# Mini_Differential_IR_Endstop_by_DC42.net
KiCad netlist of a schematic drawn in EAGLE
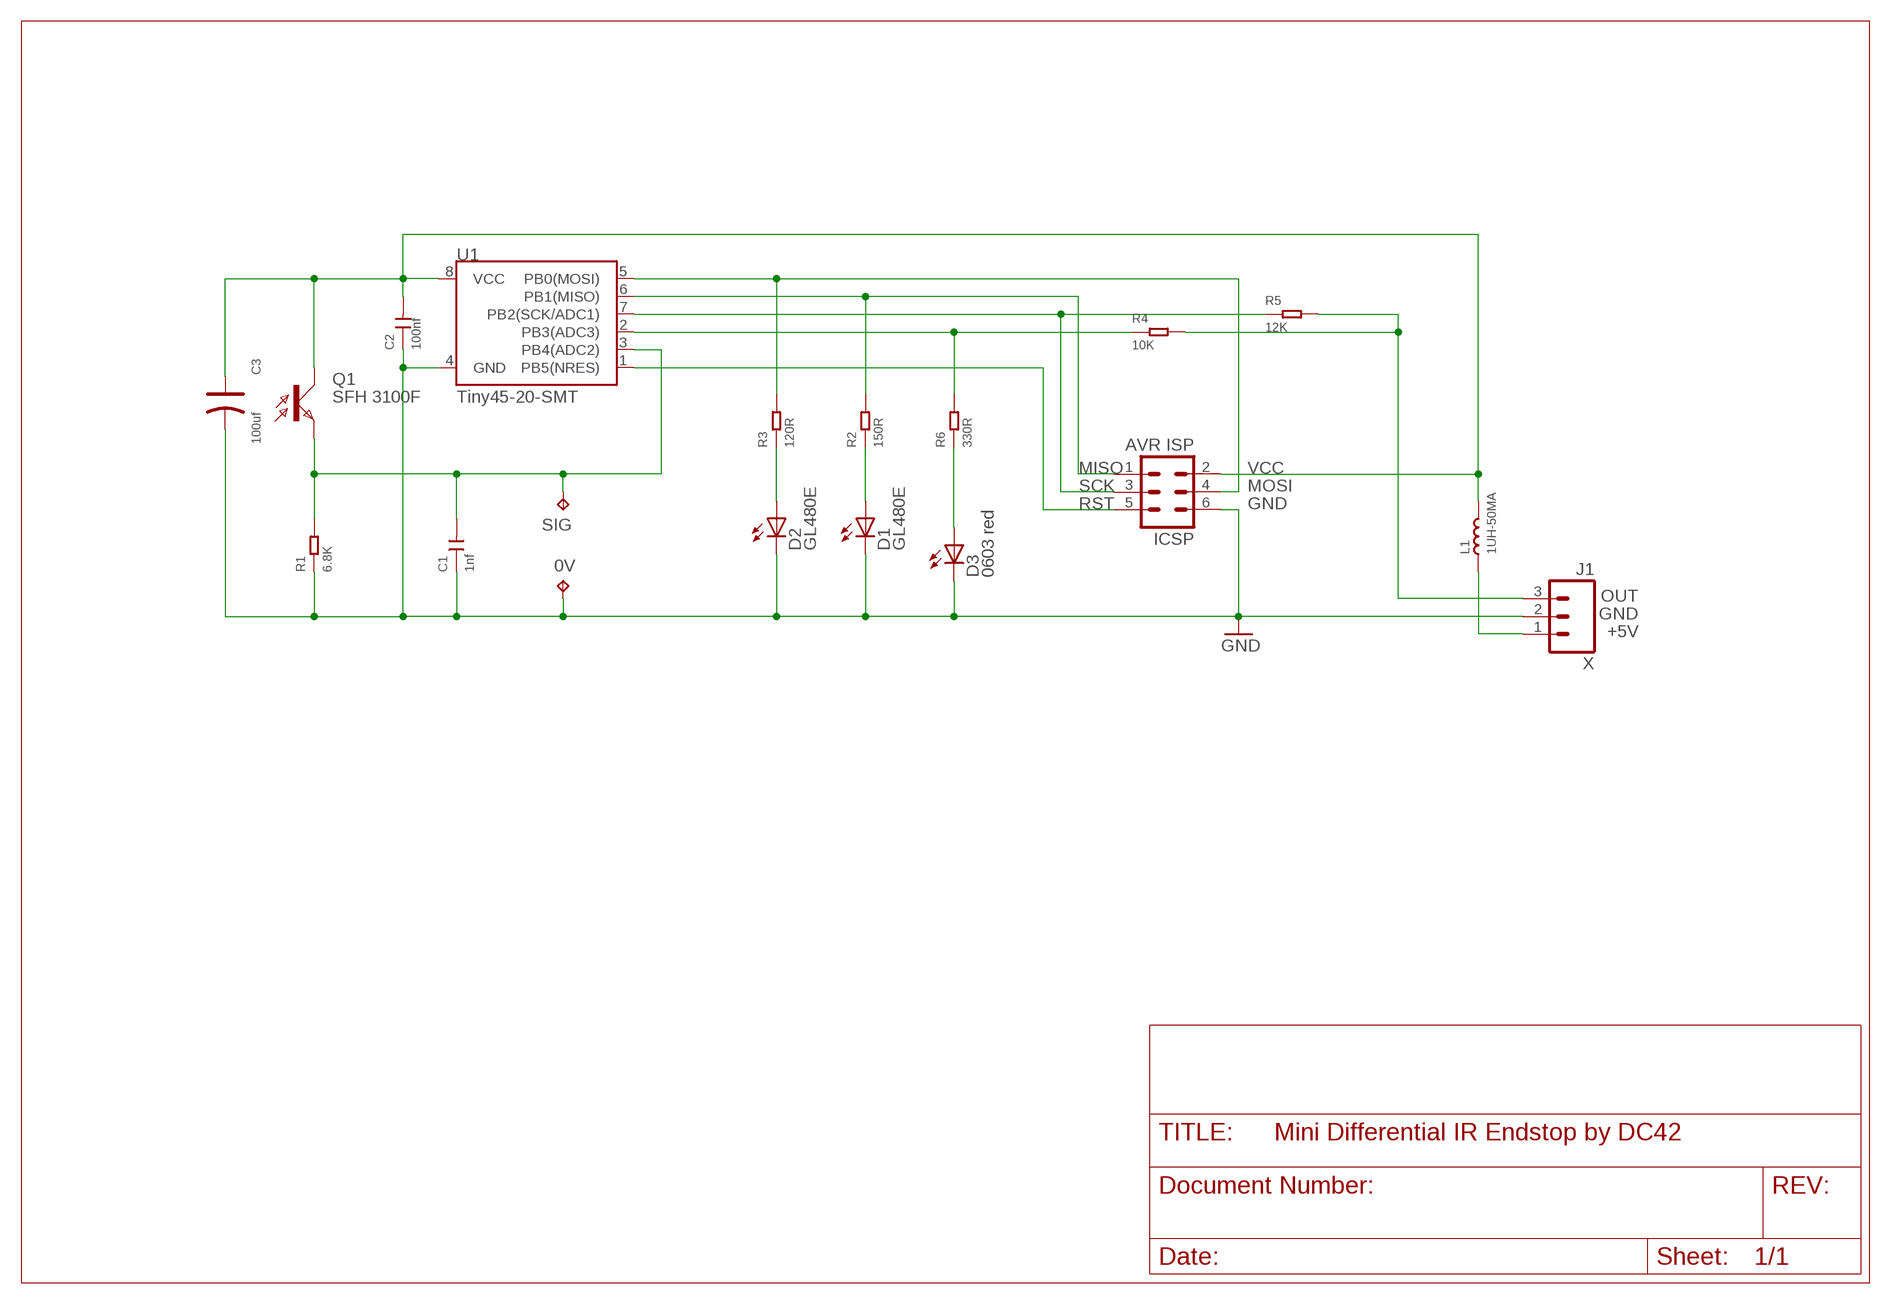
[diagram p0: schematic, sheet 1]

(export (version "E")
  (design (tool "Eeschema 10.0.6"))
  (components
    (comp (ref "0V")
      (value "TPB1,27")
      (footprint "eagle-import:B1,27")
      (libsource (lib "eagle-import") (part "TPB1,27"))
    )
    (comp (ref "C1")
      (value "1nf")
      (footprint "eagle-import:C0603")
      (fields (field (name "MPN") "GRM1885C1H102JA01D"))
      (libsource (lib "eagle-import") (part "CERAMIC-1NF-50V-5%-C0G(0603)"))
    )
    (comp (ref "C2")
      (value "100nf")
      (footprint "eagle-import:C0603")
      (fields (field (name "MPN") "CC0603KRX7R9BB104"))
      (libsource (lib "eagle-import") (part "CERAMIC-100NF-50V-10%-X7R(0603)"))
    )
    (comp (ref "C3")
      (value "100uf")
      (footprint "eagle-import:PC-D5.3MM")
      (libsource (lib "eagle-import") (part "DIP-ALUMINUM-100UF-16V(D5-H7MM)"))
    )
    (comp (ref "D1")
      (value "GL480E")
      (footprint "eagle-import:IRL80A")
      (libsource (lib "eagle-import") (part "LEDIRL80A"))
    )
    (comp (ref "D2")
      (value "GL480E")
      (footprint "eagle-import:IRL80A")
      (libsource (lib "eagle-import") (part "LEDIRL80A"))
    )
    (comp (ref "D3")
      (value "0603 red")
      (footprint "eagle-import:CHIP-LED0603")
      (libsource (lib "eagle-import") (part "LEDCHIP-LED0603"))
    )
    (comp (ref "ICSP")
      (value "AVR ISP")
      (footprint "eagle-import:MA03-2")
      (libsource (lib "eagle-import") (part "MA03-2"))
    )
    (comp (ref "J1")
      (value "X")
      (footprint "eagle-import:1X03_LOCK")
      (libsource (lib "eagle-import") (part "M03LOCK"))
    )
    (comp (ref "L1")
      (value "1UH-50MA")
      (footprint "eagle-import:L0805")
      (fields (field (name "MPN") "LQM21NN1R0K10"))
      (libsource (lib "eagle-import") (part "SMD-INDUCTOR-1UH-10%-50MA(0805)"))
    )
    (comp (ref "Q1")
      (value "SFH 3100F")
      (footprint "eagle-import:SIDELOOKER")
      (libsource (lib "eagle-import") (part "SFH3100F"))
    )
    (comp (ref "R1")
      (value "6.8K")
      (footprint "eagle-import:R0603")
      (fields (field (name "MPN") "RC0805JR-07220KL"))
      (libsource (lib "eagle-import") (part "SMD-RES-6.8K-1%-1/10W(0603)"))
    )
    (comp (ref "R2")
      (value "150R")
      (footprint "eagle-import:R0603")
      (fields (field (name "MPN") "RC0603FR-07150RL"))
      (libsource (lib "eagle-import") (part "SMD-RES-150R-1%-1/10W(0603)"))
    )
    (comp (ref "R3")
      (value "120R")
      (footprint "eagle-import:R0603")
      (fields (field (name "MPN") "RC0603FR-07120RL"))
      (libsource (lib "eagle-import") (part "SMD-RES-120R-1%-1/10W(0603)"))
    )
    (comp (ref "R4")
      (value "10K")
      (footprint "eagle-import:R0603")
      (fields (field (name "MPN") "RC0603FR-0710KL"))
      (libsource (lib "eagle-import") (part "SMD-RES-10K-1%-1/10W(0603)"))
    )
    (comp (ref "R5")
      (value "12K")
      (footprint "eagle-import:R0603")
      (fields (field (name "MPN") "RC0603FR-0712KL"))
      (libsource (lib "eagle-import") (part "SMD-RES-12K-1%-1/10W(0603)"))
    )
    (comp (ref "R6")
      (value "330R")
      (footprint "eagle-import:R0603")
      (fields (field (name "MPN") "RC0603FR-07330RL"))
      (libsource (lib "eagle-import") (part "SMD-RES-330R-1%-1/10W(0603)"))
    )
    (comp (ref "SIG")
      (value "TPB1,27")
      (footprint "eagle-import:B1,27")
      (libsource (lib "eagle-import") (part "TPB1,27"))
    )
    (comp (ref "U1")
      (value "Tiny45-20-SMT")
      (footprint "eagle-import:SO08-EIAJ")
      (libsource (lib "eagle-import") (part "ATTINY45TINY45-20-SMT"))
    )
  )
  (nets
    (net (code "1") (name "/+5V") (class "Default")
      (node (ref "J1") (pin "1") (pinfunction "1_1") (pintype "passive"))
      (node (ref "L1") (pin "1") (pinfunction "1_1") (pintype "passive"))
    )
    (net (code "2") (name "/MISO") (class "Default")
      (node (ref "ICSP") (pin "1") (pinfunction "1_1") (pintype "passive"))
      (node (ref "R2") (pin "2") (pinfunction "2_2") (pintype "passive"))
      (node (ref "U1") (pin "6") (pinfunction "PB1(MISO)_6") (pintype "bidirectional"))
    )
    (net (code "3") (name "/MOSI") (class "Default")
      (node (ref "ICSP") (pin "4") (pinfunction "4_4") (pintype "passive"))
      (node (ref "R3") (pin "2") (pinfunction "2_2") (pintype "passive"))
      (node (ref "U1") (pin "5") (pinfunction "PB0(MOSI)_5") (pintype "bidirectional"))
    )
    (net (code "4") (name "/OUT") (class "Default")
      (node (ref "J1") (pin "3") (pinfunction "3_3") (pintype "passive"))
      (node (ref "R4") (pin "2") (pinfunction "2_2") (pintype "passive"))
      (node (ref "R5") (pin "2") (pinfunction "2_2") (pintype "passive"))
    )
    (net (code "5") (name "/RST") (class "Default")
      (node (ref "ICSP") (pin "5") (pinfunction "5_5") (pintype "passive"))
      (node (ref "U1") (pin "1") (pinfunction "PB5(NRES)_1") (pintype "bidirectional"))
    )
    (net (code "6") (name "/SCK") (class "Default")
      (node (ref "ICSP") (pin "3") (pinfunction "3_3") (pintype "passive"))
      (node (ref "R5") (pin "1") (pinfunction "1_1") (pintype "passive"))
      (node (ref "U1") (pin "7") (pinfunction "PB2(SCK/ADC1)_7") (pintype "bidirectional"))
    )
    (net (code "7") (name "/VCC") (class "Default")
      (node (ref "C2") (pin "2") (pinfunction "2_2") (pintype "passive"))
      (node (ref "C3") (pin "+") (pinfunction "+_+") (pintype "passive"))
      (node (ref "ICSP") (pin "2") (pinfunction "2_2") (pintype "passive"))
      (node (ref "L1") (pin "2") (pinfunction "2_2") (pintype "passive"))
      (node (ref "Q1") (pin "A") (pinfunction "C_A") (pintype "passive"))
      (node (ref "U1") (pin "8") (pinfunction "VCC_8") (pintype "bidirectional"))
    )
    (net (code "8") (name "GND") (class "Default")
      (node (ref "0V") (pin "TP") (pinfunction "TP_TP") (pintype "input"))
      (node (ref "C1") (pin "1") (pinfunction "1_1") (pintype "passive"))
      (node (ref "C2") (pin "1") (pinfunction "1_1") (pintype "passive"))
      (node (ref "C3") (pin "-") (pinfunction "-_-") (pintype "passive"))
      (node (ref "D1") (pin "K") (pinfunction "C_K") (pintype "passive"))
      (node (ref "D2") (pin "K") (pinfunction "C_K") (pintype "passive"))
      (node (ref "D3") (pin "C") (pinfunction "C_C") (pintype "passive"))
      (node (ref "ICSP") (pin "6") (pinfunction "6_6") (pintype "passive"))
      (node (ref "J1") (pin "2") (pinfunction "2_2") (pintype "passive"))
      (node (ref "R1") (pin "1") (pinfunction "1_1") (pintype "passive"))
      (node (ref "U1") (pin "4") (pinfunction "GND_4") (pintype "bidirectional"))
    )
    (net (code "9") (name "Net-(D1-PadA)") (class "Default")
      (node (ref "D1") (pin "A") (pinfunction "A_A") (pintype "passive"))
      (node (ref "R2") (pin "1") (pinfunction "1_1") (pintype "passive"))
    )
    (net (code "10") (name "Net-(D2-PadA)") (class "Default")
      (node (ref "D2") (pin "A") (pinfunction "A_A") (pintype "passive"))
      (node (ref "R3") (pin "1") (pinfunction "1_1") (pintype "passive"))
    )
    (net (code "11") (name "Net-(D3-PadA)") (class "Default")
      (node (ref "D3") (pin "A") (pinfunction "A_A") (pintype "passive"))
      (node (ref "R6") (pin "1") (pinfunction "1_1") (pintype "passive"))
    )
    (net (code "12") (name "Net-(Q1-E)") (class "Default")
      (node (ref "C1") (pin "2") (pinfunction "2_2") (pintype "passive"))
      (node (ref "Q1") (pin "K") (pinfunction "E_K") (pintype "passive"))
      (node (ref "R1") (pin "2") (pinfunction "2_2") (pintype "passive"))
      (node (ref "SIG") (pin "TP") (pinfunction "TP_TP") (pintype "input"))
      (node (ref "U1") (pin "3") (pinfunction "PB4(ADC2)_3") (pintype "bidirectional"))
    )
    (net (code "13") (name "Net-(U1-PB3(ADC3))") (class "Default")
      (node (ref "R4") (pin "1") (pinfunction "1_1") (pintype "passive"))
      (node (ref "R6") (pin "2") (pinfunction "2_2") (pintype "passive"))
      (node (ref "U1") (pin "2") (pinfunction "PB3(ADC3)_2") (pintype "bidirectional"))
    )
  )
)
